# Votage_Reguator.net
KiCad netlist of a schematic drawn in Altium Designer
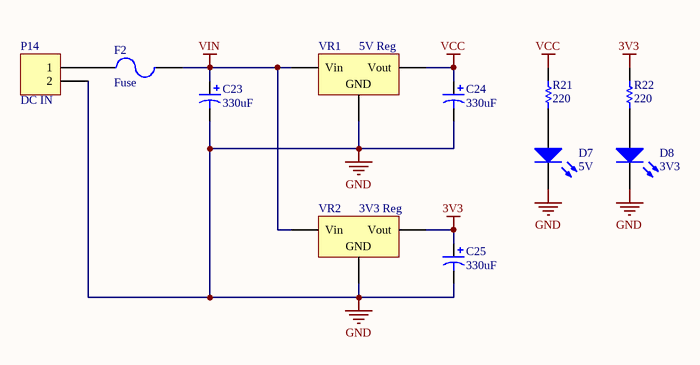
[diagram p0: Votage Reguator.SchDoc]

(export (version "E")
  (design (tool "Eeschema 10.0.6"))
  (components
    (comp (ref "C23")
      (value "330uF")
      (footprint "SV-C")
      (description "Polarized Capacitor (Axial)")
      (fields (field (name "PUBLISHER") "Altium Limited"))
      (libsource (lib "BarelangRobotics") (part "Cap Pol"))
    )
    (comp (ref "C24")
      (value "330uF")
      (footprint "SV-C")
      (description "Polarized Capacitor (Axial)")
      (fields (field (name "PUBLISHER") "Altium Limited"))
      (libsource (lib "BarelangRobotics") (part "Cap Pol"))
    )
    (comp (ref "C25")
      (value "330uF")
      (footprint "SV-C")
      (description "Polarized Capacitor (Axial)")
      (fields (field (name "PUBLISHER") "Altium Limited"))
      (libsource (lib "BarelangRobotics") (part "Cap Pol"))
    )
    (comp (ref "D7")
      (value "5V")
      (footprint "CHIPLED_0603")
      (description "Typical INFRARED GaAs LED")
      (fields (field (name "PUBLISHER") "Altium Limited"))
      (libsource (lib "BarelangRobotics") (part "LED"))
    )
    (comp (ref "D8")
      (value "3V3")
      (footprint "CHIPLED_0603")
      (description "Typical INFRARED GaAs LED")
      (fields (field (name "PUBLISHER") "Altium Limited"))
      (libsource (lib "BarelangRobotics") (part "LED"))
    )
    (comp (ref "F2")
      (value "Fuse")
      (footprint "FUSE-HOLDER-SMD")
      (fields (field (name "PUBLISHER") "Altium Limited"))
      (libsource (lib "BarelangRobotics") (part "Fuse"))
    )
    (comp (ref "P14")
      (value "DC IN")
      (footprint "DEANS")
      (description "Header, 2-Pin")
      (fields (field (name "PUBLISHER") "Altium Limited"))
      (libsource (lib "BarelangRobotics") (part "Header 2"))
    )
    (comp (ref "R21")
      (value "220")
      (footprint "0603-RES")
      (description "Resistor")
      (fields (field (name "PUBLISHER") "Altium Limited"))
      (libsource (lib "BarelangRobotics") (part "Res"))
    )
    (comp (ref "R22")
      (value "220")
      (footprint "0603-RES")
      (description "Resistor")
      (fields (field (name "PUBLISHER") "Altium Limited"))
      (libsource (lib "BarelangRobotics") (part "Res"))
    )
    (comp (ref "VR1")
      (value "5V Reg")
      (footprint "OKI-78SRH")
      (description "Voltage Regulator")
      (fields (field (name "PUBLISHER") "Altium Limited"))
      (libsource (lib "BarelangRobotics") (part "Volt Reg"))
    )
    (comp (ref "VR2")
      (value "3V3 Reg")
      (footprint "OKI-78SRH")
      (description "Voltage Regulator")
      (fields (field (name "PUBLISHER") "Altium Limited"))
      (libsource (lib "BarelangRobotics") (part "Volt Reg"))
    )
  )
  (nets
    (net (code "1") (name "3V3") (class "Default")
      (node (ref "C25") (pin "1") (pinfunction "1_1") (pintype "passive"))
      (node (ref "R22") (pin "2") (pinfunction "2_2") (pintype "passive"))
      (node (ref "VR2") (pin "3") (pinfunction "Vout_3") (pintype "passive"))
    )
    (net (code "2") (name "GND") (class "Default")
      (node (ref "C23") (pin "2") (pinfunction "2_2") (pintype "passive"))
      (node (ref "C24") (pin "2") (pinfunction "2_2") (pintype "passive"))
      (node (ref "C25") (pin "2") (pinfunction "2_2") (pintype "passive"))
      (node (ref "D7") (pin "2") (pinfunction "K_2") (pintype "passive"))
      (node (ref "D8") (pin "2") (pinfunction "K_2") (pintype "passive"))
      (node (ref "P14") (pin "2") (pinfunction "2_2") (pintype "passive"))
      (node (ref "VR1") (pin "2") (pinfunction "GND_2") (pintype "passive"))
      (node (ref "VR2") (pin "2") (pinfunction "GND_2") (pintype "passive"))
    )
    (net (code "3") (name "Net-(D7-A)") (class "Default")
      (node (ref "D7") (pin "1") (pinfunction "A_1") (pintype "passive"))
      (node (ref "R21") (pin "1") (pinfunction "1_1") (pintype "passive"))
    )
    (net (code "4") (name "Net-(D8-A)") (class "Default")
      (node (ref "D8") (pin "1") (pinfunction "A_1") (pintype "passive"))
      (node (ref "R22") (pin "1") (pinfunction "1_1") (pintype "passive"))
    )
    (net (code "5") (name "Net-(F2-Pad1)") (class "Default")
      (node (ref "F2") (pin "1") (pinfunction "1_1") (pintype "passive"))
      (node (ref "P14") (pin "1") (pinfunction "1_1") (pintype "passive"))
    )
    (net (code "6") (name "VCC") (class "Default")
      (node (ref "C24") (pin "1") (pinfunction "1_1") (pintype "passive"))
      (node (ref "R21") (pin "2") (pinfunction "2_2") (pintype "passive"))
      (node (ref "VR1") (pin "3") (pinfunction "Vout_3") (pintype "passive"))
    )
    (net (code "7") (name "VIN") (class "Default")
      (node (ref "C23") (pin "1") (pinfunction "1_1") (pintype "passive"))
      (node (ref "F2") (pin "2") (pinfunction "2_2") (pintype "passive"))
      (node (ref "VR1") (pin "1") (pinfunction "Vin_1") (pintype "passive"))
      (node (ref "VR2") (pin "1") (pinfunction "Vin_1") (pintype "passive"))
    )
  )
)
